# HIVE_BOARD_ETHERNET.net
KiCad netlist of a schematic drawn in Altium Designer
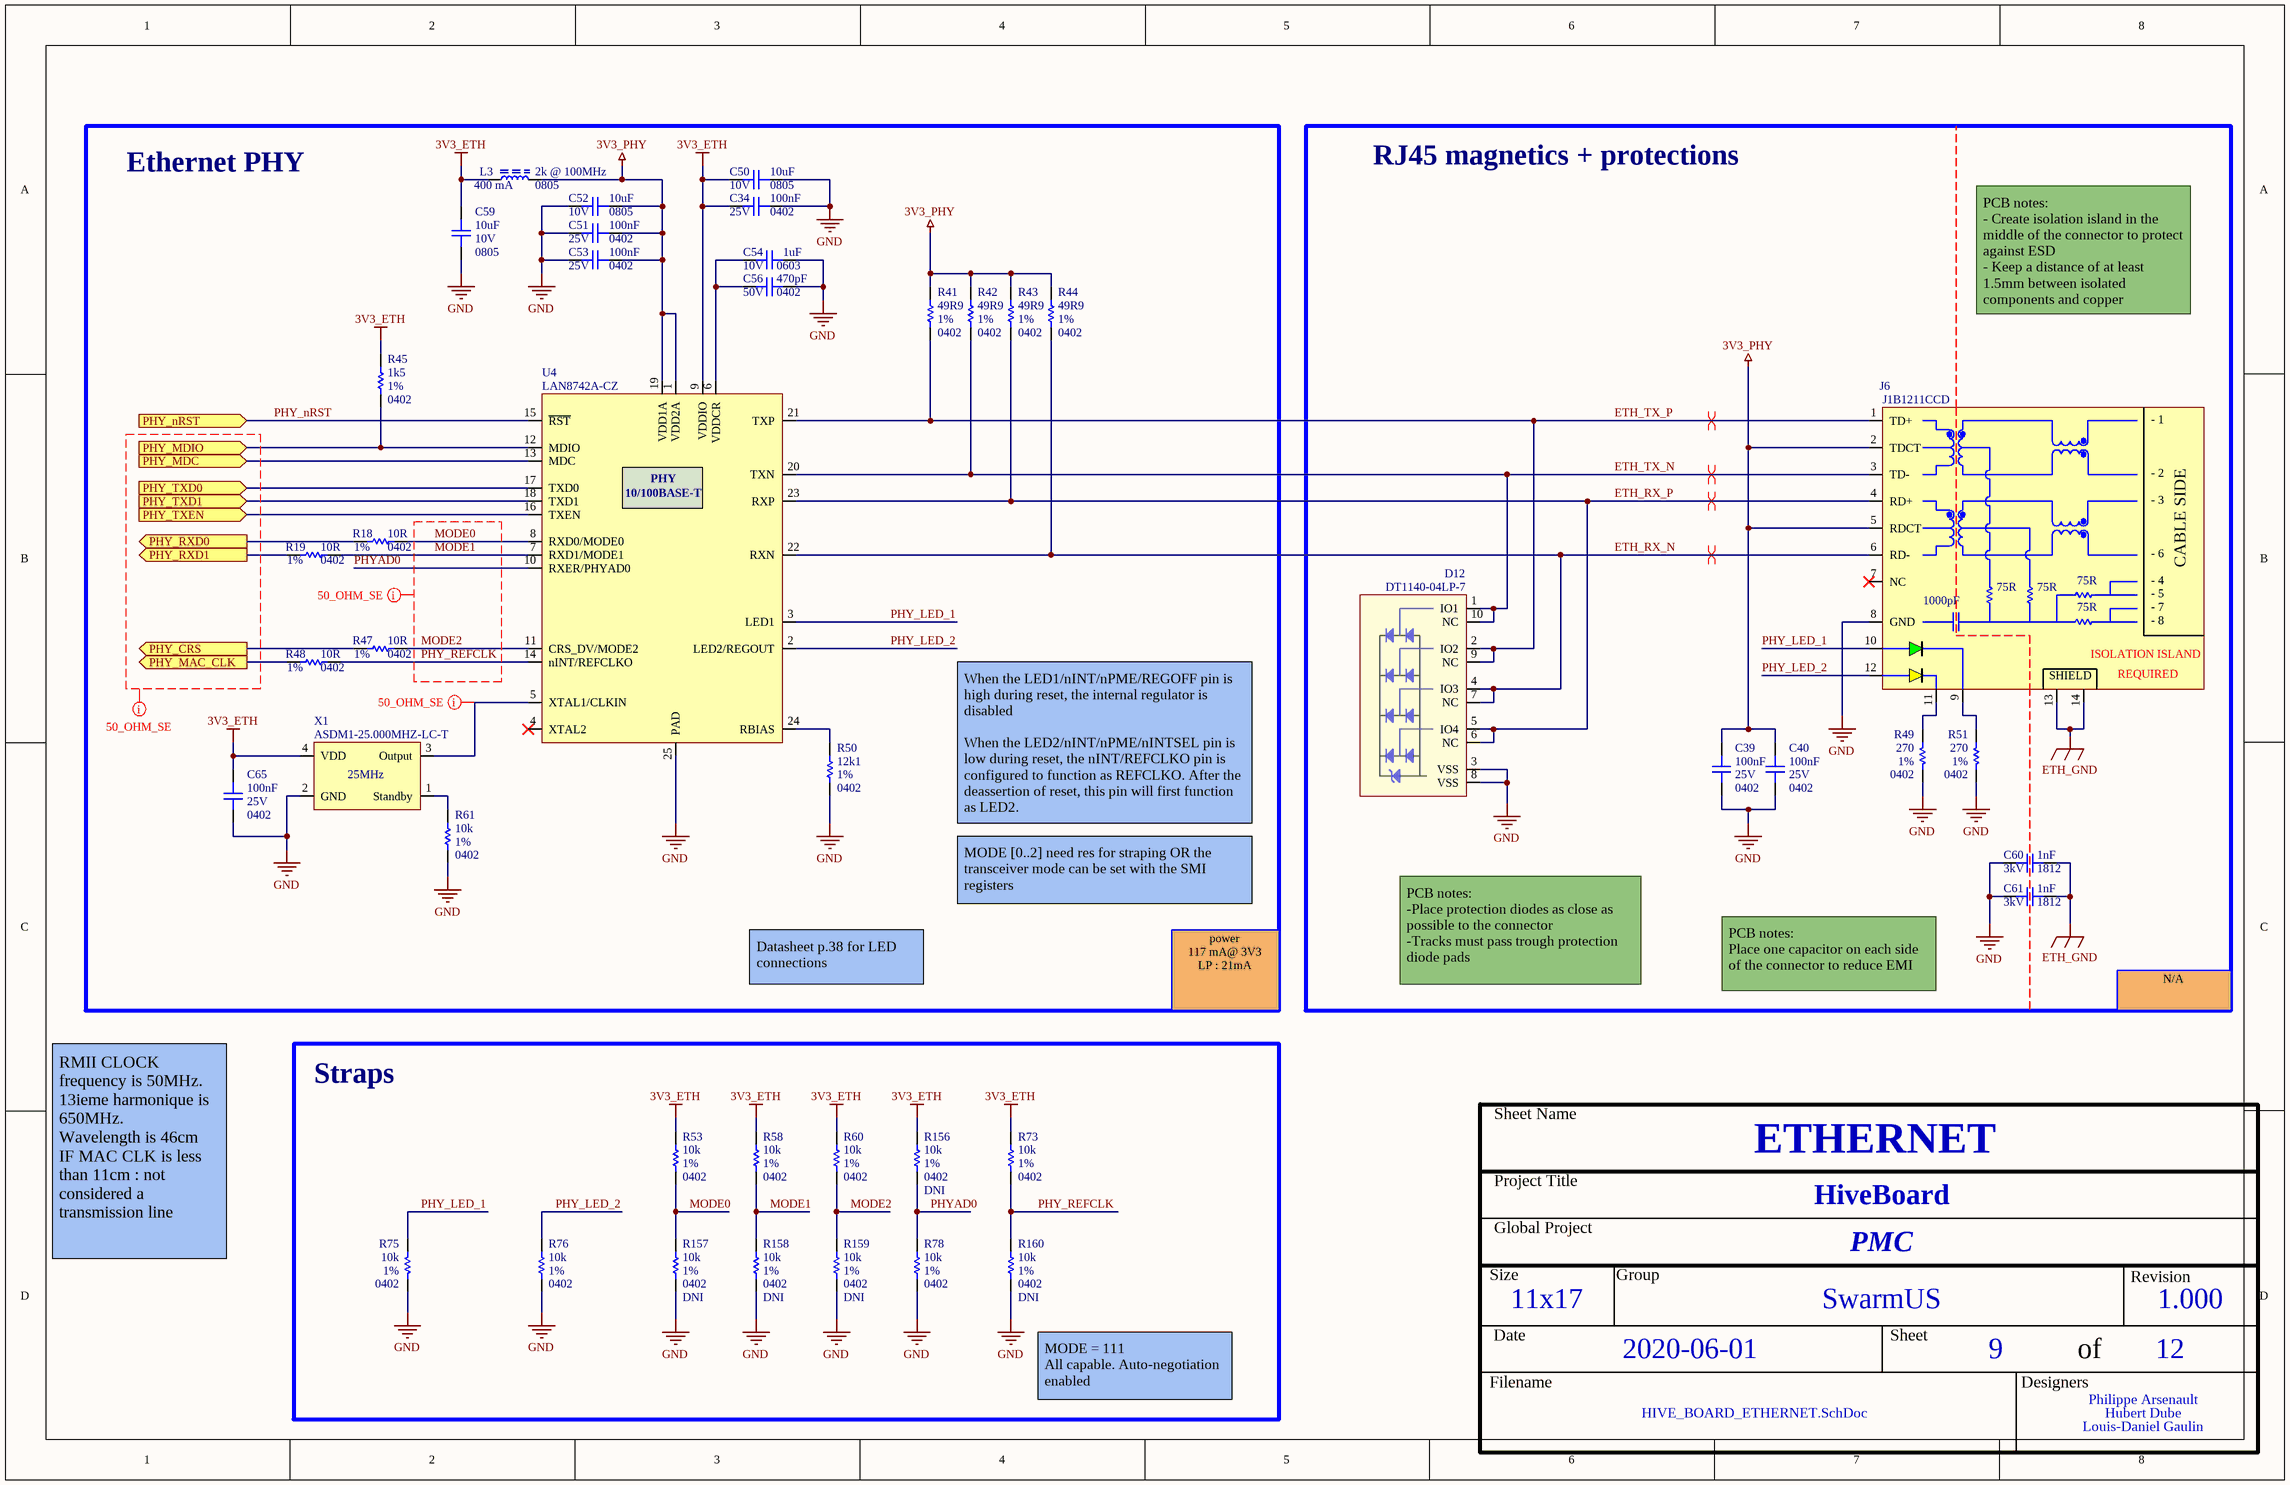
[diagram p0: HIVE_BOARD_ETHERNET.SchDoc]

(export (version "E")
  (design (tool "Eeschema 10.0.6"))
  (components
    (comp (ref "C34")
      (value "100nF")
      (footprint "CAP_CER_0402")
      (description "CAP - CER 0.1µF 10% 25V X7R - 0402")
      (fields
        (field (name "TOLERANCE") "10%")
        (field (name "PACKAGE") "0402")
        (field (name "VOLTAGE RATING") "25V")
        (field (name "Comment") "CGA2B3X7R1E104K050BB")
        (field (name "CREATEDBY/DATE") "Nicolas Roy 2018-11-07")
        (field (name "VERIFIEDBY") "Nicolas V. (2019-01-22)")
      )
      (libsource (lib "GRAMS_MASTER_LIB") (part "CAP_CER_CGA2B3X7R1E104K050BB"))
    )
    (comp (ref "C39")
      (value "100nF")
      (footprint "CAP_CER_0402")
      (description "CAP - CER 0.1µF 10% 25V X7R - 0402")
      (fields
        (field (name "TOLERANCE") "10%")
        (field (name "PACKAGE") "0402")
        (field (name "VOLTAGE RATING") "25V")
        (field (name "Comment") "CGA2B3X7R1E104K050BB")
        (field (name "CREATEDBY/DATE") "Nicolas Roy 2018-11-07")
        (field (name "VERIFIEDBY") "Nicolas V. (2019-01-22)")
      )
      (libsource (lib "GRAMS_MASTER_LIB") (part "CAP_CER_CGA2B3X7R1E104K050BB"))
    )
    (comp (ref "C40")
      (value "100nF")
      (footprint "CAP_CER_0402")
      (description "CAP - CER 0.1µF 10% 25V X7R - 0402")
      (fields
        (field (name "TOLERANCE") "10%")
        (field (name "PACKAGE") "0402")
        (field (name "VOLTAGE RATING") "25V")
        (field (name "Comment") "CGA2B3X7R1E104K050BB")
        (field (name "CREATEDBY/DATE") "Nicolas Roy 2018-11-07")
        (field (name "VERIFIEDBY") "Nicolas V. (2019-01-22)")
      )
      (libsource (lib "GRAMS_MASTER_LIB") (part "CAP_CER_CGA2B3X7R1E104K050BB"))
    )
    (comp (ref "C50")
      (value "10uF")
      (footprint "CAP_CER_0805")
      (description "CAP - CER 10UF 10% 10V X5R - 0805")
      (fields
        (field (name "TOLERANCE") "10%")
        (field (name "PACKAGE") "0805")
        (field (name "VOLTAGE RATING") "10V")
        (field (name "Comment") "LMK212BJ106KG-T")
        (field (name "CREATEDBY/DATE") "Caroline Paulin / 25 juillet 2018")
        (field (name "VERIFIEDBY") "Nicolas V. (2019-01-22)")
      )
      (libsource (lib "GRAMS_MASTER_LIB") (part "CAP_CER_LMK212BJ106KG-T"))
    )
    (comp (ref "C51")
      (value "100nF")
      (footprint "CAP_CER_0402")
      (description "CAP - CER 0.1µF 10% 25V X7R - 0402")
      (fields
        (field (name "TOLERANCE") "10%")
        (field (name "PACKAGE") "0402")
        (field (name "VOLTAGE RATING") "25V")
        (field (name "Comment") "CGA2B3X7R1E104K050BB")
        (field (name "CREATEDBY/DATE") "Nicolas Roy 2018-11-07")
        (field (name "VERIFIEDBY") "Nicolas V. (2019-01-22)")
      )
      (libsource (lib "GRAMS_MASTER_LIB") (part "CAP_CER_CGA2B3X7R1E104K050BB"))
    )
    (comp (ref "C52")
      (value "10uF")
      (footprint "CAP_CER_0805")
      (description "CAP - CER 10UF 10% 10V X5R - 0805")
      (fields
        (field (name "TOLERANCE") "10%")
        (field (name "PACKAGE") "0805")
        (field (name "VOLTAGE RATING") "10V")
        (field (name "Comment") "LMK212BJ106KG-T")
        (field (name "CREATEDBY/DATE") "Caroline Paulin / 25 juillet 2018")
        (field (name "VERIFIEDBY") "Nicolas V. (2019-01-22)")
      )
      (libsource (lib "GRAMS_MASTER_LIB") (part "CAP_CER_LMK212BJ106KG-T"))
    )
    (comp (ref "C53")
      (value "100nF")
      (footprint "CAP_CER_0402")
      (description "CAP - CER 0.1µF 10% 25V X7R - 0402")
      (fields
        (field (name "TOLERANCE") "10%")
        (field (name "PACKAGE") "0402")
        (field (name "VOLTAGE RATING") "25V")
        (field (name "Comment") "CGA2B3X7R1E104K050BB")
        (field (name "CREATEDBY/DATE") "Nicolas Roy 2018-11-07")
        (field (name "VERIFIEDBY") "Nicolas V. (2019-01-22)")
      )
      (libsource (lib "GRAMS_MASTER_LIB") (part "CAP_CER_CGA2B3X7R1E104K050BB"))
    )
    (comp (ref "C54")
      (value "1uF")
      (footprint "CAP_CER_0603")
      (description "CAP - CER 1uF 10V 10% X5R - 0603")
      (fields
        (field (name "TOLERANCE") "10%")
        (field (name "PACKAGE") "0603")
        (field (name "VOLTAGE RATING") "10V")
        (field (name "Comment") "C0603C105K8PACTU")
        (field (name "CREATEDBY/DATE") "Hubert Dube - 21/07/20")
        (field (name "VERIFIEDBY") "Louis-Daniel Gaulin - 21/07/20")
      )
      (libsource (lib "SWARMUS_LIB") (part "CAP_CER_C0603C105K8PACTU"))
    )
    (comp (ref "C56")
      (value "470pF")
      (footprint "CAP_CER_0402")
      (description "CAP - CER 470pF 10% 50V X7R - 0402")
      (fields
        (field (name "TOLERANCE") "10%")
        (field (name "PACKAGE") "0402")
        (field (name "VOLTAGE RATING") "50V")
        (field (name "Comment") "CC0402KRX7R9BB471")
        (field (name "CREATEDBY/DATE") "Nicolas Roy 2018-10-17")
        (field (name "VERIFIEDBY") "Caroline Paulin - 18 janv 2019")
      )
      (libsource (lib "GRAMS_MASTER_LIB") (part "CAP_CER_CC0402KRX7R9BB471"))
    )
    (comp (ref "C59")
      (value "10uF")
      (footprint "CAP_CER_0805")
      (description "CAP - CER 10UF 10% 10V X5R - 0805")
      (fields
        (field (name "TOLERANCE") "10%")
        (field (name "PACKAGE") "0805")
        (field (name "VOLTAGE RATING") "10V")
        (field (name "Comment") "LMK212BJ106KG-T")
        (field (name "CREATEDBY/DATE") "Caroline Paulin / 25 juillet 2018")
        (field (name "VERIFIEDBY") "Nicolas V. (2019-01-22)")
      )
      (libsource (lib "GRAMS_MASTER_LIB") (part "CAP_CER_LMK212BJ106KG-T"))
    )
    (comp (ref "C60")
      (value "1nF")
      (footprint "CAP_CER_1812")
      (description "CAP - CER 1000pF ±10% 3000V X7R")
      (fields
        (field (name "TOLERANCE") "10%")
        (field (name "PACKAGE") "1812")
        (field (name "VOLTAGE RATING") "3kV")
        (field (name "Comment") "885342211009")
        (field (name "CREATEDBY/DATE") "Hubert Dube - 03/02/2021")
        (field (name "VERIFIEDBY") "Philippe Asenault - 08-02-2021")
      )
      (libsource (lib "SWARMUS_LIB") (part "CAP_CER_885342211009"))
    )
    (comp (ref "C61")
      (value "1nF")
      (footprint "CAP_CER_1812")
      (description "CAP - CER 1000pF ±10% 3000V X7R")
      (fields
        (field (name "TOLERANCE") "10%")
        (field (name "PACKAGE") "1812")
        (field (name "VOLTAGE RATING") "3kV")
        (field (name "Comment") "885342211009")
        (field (name "CREATEDBY/DATE") "Hubert Dube - 03/02/2021")
        (field (name "VERIFIEDBY") "Philippe Asenault - 08-02-2021")
      )
      (libsource (lib "SWARMUS_LIB") (part "CAP_CER_885342211009"))
    )
    (comp (ref "C65")
      (value "100nF")
      (footprint "CAP_CER_0402")
      (description "CAP - CER 0.1µF 10% 25V X7R - 0402")
      (fields
        (field (name "TOLERANCE") "10%")
        (field (name "PACKAGE") "0402")
        (field (name "VOLTAGE RATING") "25V")
        (field (name "Comment") "CGA2B3X7R1E104K050BB")
        (field (name "CREATEDBY/DATE") "Nicolas Roy 2018-11-07")
        (field (name "VERIFIEDBY") "Nicolas V. (2019-01-22)")
      )
      (libsource (lib "GRAMS_MASTER_LIB") (part "CAP_CER_CGA2B3X7R1E104K050BB"))
    )
    (comp (ref "D12")
      (value "DT1140-04LP-7")
      (footprint "TVS_DATA_DT1140-04LP-7")
      (description "TVS - DIODE 5.5V 10V - 10-UFDFN")
      (fields
        (field (name "CREATEDBY/DATE") "Joël Lemay 2019-11-20")
        (field (name "VERIFIEDBY") "C.Paulin - 21/11/2019")
      )
      (libsource (lib "GRAMS_MASTER_LIB") (part "TVS_DATA_DT1140-04LP-7"))
    )
    (comp (ref "J6")
      (value "J1B1211CCD")
      (footprint "CON_ETH_J1B1211CCD_WIZ")
      (fields
        (field (name "CREATEDBY/DATE") "Hubert Dube - 12/02/2021")
        (field (name "VERIFIEDBY") "Philippe Arsenault - 2021-03-10")
      )
      (libsource (lib "SWARMUS_LIB") (part "CON_ETH_J1B1211CCD"))
    )
    (comp (ref "L3")
      (value "2k @ 100MHz")
      (footprint "FER_0805")
      (description "FER - FERRITE BEAD 2 KOHM @ 100 MHz 400 mA - 0805")
      (fields
        (field (name "CURRENT RATING") "400 mA")
        (field (name "PACKAGE") "0805")
        (field (name "Comment") "MMZ2012Y202BT000")
        (field (name "CREATEDBY/DATE") "Hubert Dube - 7/02/2021")
        (field (name "VERIFIEDBY") "Philippe Arsenault/ 2021-03-13")
      )
      (libsource (lib "SWARMUS_LIB") (part "FER_MMZ2012Y202BT000"))
    )
    (comp (ref "R18")
      (value "10R")
      (footprint "RES_0402")
      (description "RES - 10R 1% 1/16W - 0402")
      (fields
        (field (name "TOLERANCE") "1%")
        (field (name "PACKAGE") "0402")
        (field (name "Comment") "RMCF0402FT10R0")
        (field (name "CREATEDBY/DATE") "Joel Lemay 2018-07-04")
        (field (name "VERIFIEDBY") "Caroline Paulin - 6 sept 2018")
      )
      (libsource (lib "GRAMS_MASTER_LIB") (part "RES_RMCF0402FT10R0"))
    )
    (comp (ref "R19")
      (value "10R")
      (footprint "RES_0402")
      (description "RES - 10R 1% 1/16W - 0402")
      (fields
        (field (name "TOLERANCE") "1%")
        (field (name "PACKAGE") "0402")
        (field (name "Comment") "RMCF0402FT10R0")
        (field (name "CREATEDBY/DATE") "Joel Lemay 2018-07-04")
        (field (name "VERIFIEDBY") "Caroline Paulin - 6 sept 2018")
      )
      (libsource (lib "GRAMS_MASTER_LIB") (part "RES_RMCF0402FT10R0"))
    )
    (comp (ref "R41")
      (value "49R9")
      (footprint "RES_0402")
      (description "RES - 49.9 R ±1% 1/16W -  0402")
      (fields
        (field (name "TOLERANCE") "1%")
        (field (name "PACKAGE") "0402")
        (field (name "Comment") "RC0402FR-0749R9L")
        (field (name "CREATEDBY/DATE") "Hubert Dubé - 3/02/2020")
        (field (name "VERIFIEDBY") "Philippe Arsenault/2021-02-08")
      )
      (libsource (lib "SWARMUS_LIB") (part "RES_RC0402FR-0749R9L"))
    )
    (comp (ref "R42")
      (value "49R9")
      (footprint "RES_0402")
      (description "RES - 49.9 R ±1% 1/16W -  0402")
      (fields
        (field (name "TOLERANCE") "1%")
        (field (name "PACKAGE") "0402")
        (field (name "Comment") "RC0402FR-0749R9L")
        (field (name "CREATEDBY/DATE") "Hubert Dubé - 3/02/2020")
        (field (name "VERIFIEDBY") "Philippe Arsenault/2021-02-08")
      )
      (libsource (lib "SWARMUS_LIB") (part "RES_RC0402FR-0749R9L"))
    )
    (comp (ref "R43")
      (value "49R9")
      (footprint "RES_0402")
      (description "RES - 49.9 R ±1% 1/16W -  0402")
      (fields
        (field (name "TOLERANCE") "1%")
        (field (name "PACKAGE") "0402")
        (field (name "Comment") "RC0402FR-0749R9L")
        (field (name "CREATEDBY/DATE") "Hubert Dubé - 3/02/2020")
        (field (name "VERIFIEDBY") "Philippe Arsenault/2021-02-08")
      )
      (libsource (lib "SWARMUS_LIB") (part "RES_RC0402FR-0749R9L"))
    )
    (comp (ref "R44")
      (value "49R9")
      (footprint "RES_0402")
      (description "RES - 49.9 R ±1% 1/16W -  0402")
      (fields
        (field (name "TOLERANCE") "1%")
        (field (name "PACKAGE") "0402")
        (field (name "Comment") "RC0402FR-0749R9L")
        (field (name "CREATEDBY/DATE") "Hubert Dubé - 3/02/2020")
        (field (name "VERIFIEDBY") "Philippe Arsenault/2021-02-08")
      )
      (libsource (lib "SWARMUS_LIB") (part "RES_RC0402FR-0749R9L"))
    )
    (comp (ref "R45")
      (value "1k5")
      (footprint "RES_0402")
      (description "RES - 1.5K 1% 1/16W - 0402")
      (fields
        (field (name "TOLERANCE") "1%")
        (field (name "PACKAGE") "0402")
        (field (name "Comment") "RC0402FR-071K5L")
        (field (name "CREATEDBY/DATE") "Philippe Arsenault/21 Janvier 2020")
        (field (name "VERIFIEDBY") "C.Paulin - 28/01/2020")
      )
      (libsource (lib "GRAMS_MASTER_LIB") (part "RES_RC0402FR-071K5L"))
    )
    (comp (ref "R47")
      (value "10R")
      (footprint "RES_0402")
      (description "RES - 10R 1% 1/16W - 0402")
      (fields
        (field (name "TOLERANCE") "1%")
        (field (name "PACKAGE") "0402")
        (field (name "Comment") "RMCF0402FT10R0")
        (field (name "CREATEDBY/DATE") "Joel Lemay 2018-07-04")
        (field (name "VERIFIEDBY") "Caroline Paulin - 6 sept 2018")
      )
      (libsource (lib "GRAMS_MASTER_LIB") (part "RES_RMCF0402FT10R0"))
    )
    (comp (ref "R48")
      (value "10R")
      (footprint "RES_0402")
      (description "RES - 10R 1% 1/16W - 0402")
      (fields
        (field (name "TOLERANCE") "1%")
        (field (name "PACKAGE") "0402")
        (field (name "Comment") "RMCF0402FT10R0")
        (field (name "CREATEDBY/DATE") "Joel Lemay 2018-07-04")
        (field (name "VERIFIEDBY") "Caroline Paulin - 6 sept 2018")
      )
      (libsource (lib "GRAMS_MASTER_LIB") (part "RES_RMCF0402FT10R0"))
    )
    (comp (ref "R49")
      (value "270")
      (footprint "FER_0402")
      (description "RES - 270R 1% 1/16W - 0402")
      (fields
        (field (name "TOLERANCE") "1%")
        (field (name "PACKAGE") "0402")
        (field (name "Comment") "RC0402FR-07270RL")
        (field (name "CREATEDBY/DATE") "Philippe Arsenault 2020-07-24")
        (field (name "VERIFIEDBY") "Louis-Daniel Gaulin / 03-10-2020")
      )
      (libsource (lib "SWARMUS_LIB") (part "RES_RC0402FR-07270RL"))
    )
    (comp (ref "R50")
      (value "12k1")
      (footprint "RES_0402")
      (description "RES - 12K1 ±1% 1/16W - 0402")
      (fields
        (field (name "TOLERANCE") "1%")
        (field (name "PACKAGE") "0402")
        (field (name "Comment") "RC0402FR-0712K1L")
        (field (name "CREATEDBY/DATE") "Hubert Dubé - 7/02/2020")
        (field (name "VERIFIEDBY") "Philippe Arsenault/2021-02-08")
      )
      (libsource (lib "SWARMUS_LIB") (part "RES_RC0402FR-0712K1L"))
    )
    (comp (ref "R51")
      (value "270")
      (footprint "FER_0402")
      (description "RES - 270R 1% 1/16W - 0402")
      (fields
        (field (name "TOLERANCE") "1%")
        (field (name "PACKAGE") "0402")
        (field (name "Comment") "RC0402FR-07270RL")
        (field (name "CREATEDBY/DATE") "Philippe Arsenault 2020-07-24")
        (field (name "VERIFIEDBY") "Louis-Daniel Gaulin / 03-10-2020")
      )
      (libsource (lib "SWARMUS_LIB") (part "RES_RC0402FR-07270RL"))
    )
    (comp (ref "R53")
      (value "10k")
      (footprint "RES_0402")
      (description "RES - 10K OHMS 1% 1/16W - 0402")
      (fields
        (field (name "TOLERANCE") "1%")
        (field (name "PACKAGE") "0402")
        (field (name "Comment") "RC0402FR-0710KL")
        (field (name "CREATEDBY/DATE") "Nicolas V. (2018-11-20)")
        (field (name "VERIFIEDBY") "Nicolas V. (2018-11-20)")
      )
      (libsource (lib "GRAMS_MASTER_LIB") (part "RES_RC0402FR-0710KL"))
    )
    (comp (ref "R58")
      (value "10k")
      (footprint "RES_0402")
      (description "RES - 10K OHMS 1% 1/16W - 0402")
      (fields
        (field (name "TOLERANCE") "1%")
        (field (name "PACKAGE") "0402")
        (field (name "Comment") "RC0402FR-0710KL")
        (field (name "CREATEDBY/DATE") "Nicolas V. (2018-11-20)")
        (field (name "VERIFIEDBY") "Nicolas V. (2018-11-20)")
      )
      (libsource (lib "GRAMS_MASTER_LIB") (part "RES_RC0402FR-0710KL"))
    )
    (comp (ref "R60")
      (value "10k")
      (footprint "RES_0402")
      (description "RES - 10K OHMS 1% 1/16W - 0402")
      (fields
        (field (name "TOLERANCE") "1%")
        (field (name "PACKAGE") "0402")
        (field (name "Comment") "RC0402FR-0710KL")
        (field (name "CREATEDBY/DATE") "Nicolas V. (2018-11-20)")
        (field (name "VERIFIEDBY") "Nicolas V. (2018-11-20)")
      )
      (libsource (lib "GRAMS_MASTER_LIB") (part "RES_RC0402FR-0710KL"))
    )
    (comp (ref "R61")
      (value "10k")
      (footprint "RES_0402")
      (description "RES - 10K OHMS 1% 1/16W - 0402")
      (fields
        (field (name "TOLERANCE") "1%")
        (field (name "PACKAGE") "0402")
        (field (name "Comment") "RC0402FR-0710KL")
        (field (name "CREATEDBY/DATE") "Nicolas V. (2018-11-20)")
        (field (name "VERIFIEDBY") "Nicolas V. (2018-11-20)")
      )
      (libsource (lib "GRAMS_MASTER_LIB") (part "RES_RC0402FR-0710KL"))
    )
    (comp (ref "R73")
      (value "10k")
      (footprint "RES_0402")
      (description "RES - 10K OHMS 1% 1/16W - 0402")
      (fields
        (field (name "TOLERANCE") "1%")
        (field (name "PACKAGE") "0402")
        (field (name "Comment") "RC0402FR-0710KL")
        (field (name "CREATEDBY/DATE") "Nicolas V. (2018-11-20)")
        (field (name "VERIFIEDBY") "Nicolas V. (2018-11-20)")
      )
      (libsource (lib "GRAMS_MASTER_LIB") (part "RES_RC0402FR-0710KL"))
    )
    (comp (ref "R75")
      (value "10k")
      (footprint "RES_0402")
      (description "RES - 10K OHMS 1% 1/16W - 0402")
      (fields
        (field (name "TOLERANCE") "1%")
        (field (name "PACKAGE") "0402")
        (field (name "Comment") "RC0402FR-0710KL")
        (field (name "CREATEDBY/DATE") "Nicolas V. (2018-11-20)")
        (field (name "VERIFIEDBY") "Nicolas V. (2018-11-20)")
      )
      (libsource (lib "GRAMS_MASTER_LIB") (part "RES_RC0402FR-0710KL"))
    )
    (comp (ref "R76")
      (value "10k")
      (footprint "RES_0402")
      (description "RES - 10K OHMS 1% 1/16W - 0402")
      (fields
        (field (name "TOLERANCE") "1%")
        (field (name "PACKAGE") "0402")
        (field (name "Comment") "RC0402FR-0710KL")
        (field (name "CREATEDBY/DATE") "Nicolas V. (2018-11-20)")
        (field (name "VERIFIEDBY") "Nicolas V. (2018-11-20)")
      )
      (libsource (lib "GRAMS_MASTER_LIB") (part "RES_RC0402FR-0710KL"))
    )
    (comp (ref "R78")
      (value "10k")
      (footprint "RES_0402")
      (description "RES - 10K OHMS 1% 1/16W - 0402")
      (fields
        (field (name "TOLERANCE") "1%")
        (field (name "PACKAGE") "0402")
        (field (name "Comment") "RC0402FR-0710KL")
        (field (name "CREATEDBY/DATE") "Nicolas V. (2018-11-20)")
        (field (name "VERIFIEDBY") "Nicolas V. (2018-11-20)")
      )
      (libsource (lib "GRAMS_MASTER_LIB") (part "RES_RC0402FR-0710KL"))
    )
    (comp (ref "R156")
      (value "10k")
      (footprint "RES_0402")
      (description "RES - 10K OHMS 1% 1/16W - 0402")
      (fields
        (field (name "TOLERANCE") "1%")
        (field (name "ASSEMBLY NOTE") "DNI")
        (field (name "PACKAGE") "0402")
        (field (name "Comment") "RC0402FR-0710KL")
        (field (name "CREATEDBY/DATE") "Nicolas V. (2018-11-20)")
        (field (name "VERIFIEDBY") "Nicolas V. (2018-11-20)")
      )
      (libsource (lib "GRAMS_MASTER_LIB") (part "RES_RC0402FR-0710KL"))
    )
    (comp (ref "R157")
      (value "10k")
      (footprint "RES_0402")
      (description "RES - 10K OHMS 1% 1/16W - 0402")
      (fields
        (field (name "TOLERANCE") "1%")
        (field (name "ASSEMBLY NOTE") "DNI")
        (field (name "PACKAGE") "0402")
        (field (name "Comment") "RC0402FR-0710KL")
        (field (name "CREATEDBY/DATE") "Nicolas V. (2018-11-20)")
        (field (name "VERIFIEDBY") "Nicolas V. (2018-11-20)")
      )
      (libsource (lib "GRAMS_MASTER_LIB") (part "RES_RC0402FR-0710KL"))
    )
    (comp (ref "R158")
      (value "10k")
      (footprint "RES_0402")
      (description "RES - 10K OHMS 1% 1/16W - 0402")
      (fields
        (field (name "TOLERANCE") "1%")
        (field (name "ASSEMBLY NOTE") "DNI")
        (field (name "PACKAGE") "0402")
        (field (name "Comment") "RC0402FR-0710KL")
        (field (name "CREATEDBY/DATE") "Nicolas V. (2018-11-20)")
        (field (name "VERIFIEDBY") "Nicolas V. (2018-11-20)")
      )
      (libsource (lib "GRAMS_MASTER_LIB") (part "RES_RC0402FR-0710KL"))
    )
    (comp (ref "R159")
      (value "10k")
      (footprint "RES_0402")
      (description "RES - 10K OHMS 1% 1/16W - 0402")
      (fields
        (field (name "TOLERANCE") "1%")
        (field (name "ASSEMBLY NOTE") "DNI")
        (field (name "PACKAGE") "0402")
        (field (name "Comment") "RC0402FR-0710KL")
        (field (name "CREATEDBY/DATE") "Nicolas V. (2018-11-20)")
        (field (name "VERIFIEDBY") "Nicolas V. (2018-11-20)")
      )
      (libsource (lib "GRAMS_MASTER_LIB") (part "RES_RC0402FR-0710KL"))
    )
    (comp (ref "R160")
      (value "10k")
      (footprint "RES_0402")
      (description "RES - 10K OHMS 1% 1/16W - 0402")
      (fields
        (field (name "TOLERANCE") "1%")
        (field (name "ASSEMBLY NOTE") "DNI")
        (field (name "PACKAGE") "0402")
        (field (name "Comment") "RC0402FR-0710KL")
        (field (name "CREATEDBY/DATE") "Nicolas V. (2018-11-20)")
        (field (name "VERIFIEDBY") "Nicolas V. (2018-11-20)")
      )
      (libsource (lib "GRAMS_MASTER_LIB") (part "RES_RC0402FR-0710KL"))
    )
    (comp (ref "U4")
      (value "LAN8742A-CZ")
      (footprint "COM_ETH_LAN8742A-CZ-TR")
      (description "COM_ETH_ Ethernet PHY 1/1 Transceiver  Ethernet 24-SQFN (4x4) 10/100 BASE-T")
      (fields
        (field (name "VERIFIEDBY") "Philippe Arsenault 2021-03-10")
        (field (name "CREATEDBY/DATE") "Hubert Dube -  28/01/2021")
      )
      (libsource (lib "SWARMUS_LIB") (part "COM_ETH_LAN8742A-CZ"))
    )
    (comp (ref "X1")
      (value "ASDM1-25.000MHZ-LC-T")
      (footprint "OSC_CRY_ASDM1-25.000MHZ-LC-T")
      (description "OSC_CRY - 25MHz +-50ppm LVCMOS Crystal")
      (fields
        (field (name "CREATEDBY/DATE") "Philippe Arsenault/2021-04-07")
        (field (name "VERIFIEDBY") "Louis-Daniel Gaulin / 08-04-2021")
      )
      (libsource (lib "SWARMUS_LIB") (part "OSC_CRY_ASDM1-25.000MHZ-LC-T"))
    )
  )
  (nets
    (net (code "1") (name "/ETH_RX_N") (class "Default")
      (node (ref "D12") (pin "4") (pinfunction "IO3_4") (pintype "passive"))
      (node (ref "D12") (pin "7") (pinfunction "NC_7") (pintype "passive"))
      (node (ref "J6") (pin "6") (pinfunction "RD-_6") (pintype "passive"))
      (node (ref "R44") (pin "1") (pinfunction "1_1") (pintype "passive"))
      (node (ref "U4") (pin "22") (pinfunction "RXN_22") (pintype "passive"))
    )
    (net (code "2") (name "/ETH_RX_P") (class "Default")
      (node (ref "D12") (pin "5") (pinfunction "IO4_5") (pintype "passive"))
      (node (ref "D12") (pin "6") (pinfunction "NC_6") (pintype "passive"))
      (node (ref "J6") (pin "4") (pinfunction "RD+_4") (pintype "passive"))
      (node (ref "R43") (pin "1") (pinfunction "1_1") (pintype "passive"))
      (node (ref "U4") (pin "23") (pinfunction "RXP_23") (pintype "passive"))
    )
    (net (code "3") (name "/ETH_TX_N") (class "Default")
      (node (ref "D12") (pin "1") (pinfunction "IO1_1") (pintype "passive"))
      (node (ref "D12") (pin "10") (pinfunction "NC_10") (pintype "passive"))
      (node (ref "J6") (pin "3") (pinfunction "TD-_3") (pintype "passive"))
      (node (ref "R42") (pin "1") (pinfunction "1_1") (pintype "passive"))
      (node (ref "U4") (pin "20") (pinfunction "TXN_20") (pintype "passive"))
    )
    (net (code "4") (name "/ETH_TX_P") (class "Default")
      (node (ref "D12") (pin "2") (pinfunction "IO2_2") (pintype "passive"))
      (node (ref "D12") (pin "9") (pinfunction "NC_9") (pintype "passive"))
      (node (ref "J6") (pin "1") (pinfunction "TD+_1") (pintype "passive"))
      (node (ref "R41") (pin "1") (pinfunction "1_1") (pintype "passive"))
      (node (ref "U4") (pin "21") (pinfunction "TXP_21") (pintype "passive"))
    )
    (net (code "5") (name "/MODE0") (class "Default")
      (node (ref "R157") (pin "2") (pinfunction "2_2") (pintype "passive"))
      (node (ref "R18") (pin "1") (pinfunction "1_1") (pintype "passive"))
      (node (ref "R53") (pin "1") (pinfunction "1_1") (pintype "passive"))
      (node (ref "U4") (pin "8") (pinfunction "RXD0/MODE0_8") (pintype "passive"))
    )
    (net (code "6") (name "/MODE1") (class "Default")
      (node (ref "R158") (pin "2") (pinfunction "2_2") (pintype "passive"))
      (node (ref "R19") (pin "1") (pinfunction "1_1") (pintype "passive"))
      (node (ref "R58") (pin "1") (pinfunction "1_1") (pintype "passive"))
      (node (ref "U4") (pin "7") (pinfunction "RXD1/MODE1_7") (pintype "passive"))
    )
    (net (code "7") (name "/MODE2") (class "Default")
      (node (ref "R159") (pin "2") (pinfunction "2_2") (pintype "passive"))
      (node (ref "R47") (pin "1") (pinfunction "1_1") (pintype "passive"))
      (node (ref "R60") (pin "1") (pinfunction "1_1") (pintype "passive"))
      (node (ref "U4") (pin "11") (pinfunction "CRS_DV/MODE2_11") (pintype "passive"))
    )
    (net (code "8") (name "/PHYAD0") (class "Default")
      (node (ref "R156") (pin "1") (pinfunction "1_1") (pintype "passive"))
      (node (ref "R78") (pin "2") (pinfunction "2_2") (pintype "passive"))
      (node (ref "U4") (pin "10") (pinfunction "RXER/PHYAD0_10") (pintype "passive"))
    )
    (net (code "9") (name "/PHY_CRS") (class "Default")
      (node (ref "R47") (pin "2") (pinfunction "2_2") (pintype "passive"))
    )
    (net (code "10") (name "/PHY_LED_1") (class "Default")
      (node (ref "J6") (pin "10") (pinfunction "LED1_A_10") (pintype "passive"))
      (node (ref "R75") (pin "2") (pinfunction "2_2") (pintype "passive"))
      (node (ref "U4") (pin "3") (pinfunction "LED1_3") (pintype "passive"))
    )
    (net (code "11") (name "/PHY_LED_2") (class "Default")
      (node (ref "J6") (pin "12") (pintype "passive"))
      (node (ref "R76") (pin "2") (pinfunction "2_2") (pintype "passive"))
      (node (ref "U4") (pin "2") (pinfunction "LED2/REGOUT_2") (pintype "passive"))
    )
    (net (code "12") (name "/PHY_MAC_CLK") (class "Default")
      (node (ref "R48") (pin "2") (pinfunction "2_2") (pintype "passive"))
    )
    (net (code "13") (name "/PHY_MDC") (class "Default")
      (node (ref "U4") (pin "13") (pinfunction "MDC_13") (pintype "passive"))
    )
    (net (code "14") (name "/PHY_MDIO") (class "Default")
      (node (ref "R45") (pin "1") (pinfunction "1_1") (pintype "passive"))
      (node (ref "U4") (pin "12") (pinfunction "MDIO_12") (pintype "passive"))
    )
    (net (code "15") (name "/PHY_REFCLK") (class "Default")
      (node (ref "R160") (pin "2") (pinfunction "2_2") (pintype "passive"))
      (node (ref "R48") (pin "1") (pinfunction "1_1") (pintype "passive"))
      (node (ref "R73") (pin "1") (pinfunction "1_1") (pintype "passive"))
      (node (ref "U4") (pin "14") (pinfunction "nINT/REFCLKO_14") (pintype "passive"))
    )
    (net (code "16") (name "/PHY_RXD0") (class "Default")
      (node (ref "R18") (pin "2") (pinfunction "2_2") (pintype "passive"))
    )
    (net (code "17") (name "/PHY_RXD1") (class "Default")
      (node (ref "R19") (pin "2") (pinfunction "2_2") (pintype "passive"))
    )
    (net (code "18") (name "/PHY_TXD0") (class "Default")
      (node (ref "U4") (pin "17") (pinfunction "TXD0_17") (pintype "passive"))
    )
    (net (code "19") (name "/PHY_TXD1") (class "Default")
      (node (ref "U4") (pin "18") (pinfunction "TXD1_18") (pintype "passive"))
    )
    (net (code "20") (name "/PHY_TXEN") (class "Default")
      (node (ref "U4") (pin "16") (pinfunction "TXEN_16") (pintype "passive"))
    )
    (net (code "21") (name "/PHY_nRST") (class "Default")
      (node (ref "U4") (pin "15") (pinfunction "RST_15") (pintype "passive"))
    )
    (net (code "22") (name "3V3_ETH") (class "Default")
      (node (ref "C34") (pin "2") (pinfunction "2_2") (pintype "passive"))
      (node (ref "C50") (pin "2") (pinfunction "2_2") (pintype "passive"))
      (node (ref "C59") (pin "2") (pinfunction "2_2") (pintype "passive"))
      (node (ref "C65") (pin "1") (pinfunction "1_1") (pintype "passive"))
      (node (ref "L3") (pin "1") (pinfunction "1_1") (pintype "passive"))
      (node (ref "R156") (pin "2") (pinfunction "2_2") (pintype "passive"))
      (node (ref "R45") (pin "2") (pinfunction "2_2") (pintype "passive"))
      (node (ref "R53") (pin "2") (pinfunction "2_2") (pintype "passive"))
      (node (ref "R58") (pin "2") (pinfunction "2_2") (pintype "passive"))
      (node (ref "R60") (pin "2") (pinfunction "2_2") (pintype "passive"))
      (node (ref "R73") (pin "2") (pinfunction "2_2") (pintype "passive"))
      (node (ref "U4") (pin "9") (pinfunction "VDDIO_9") (pintype "passive"))
      (node (ref "X1") (pin "4") (pinfunction "VDD_4") (pintype "passive"))
    )
    (net (code "23") (name "3V3_PHY") (class "Default")
      (node (ref "C39") (pin "1") (pinfunction "1_1") (pintype "passive"))
      (node (ref "C40") (pin "1") (pinfunction "1_1") (pintype "passive"))
      (node (ref "C51") (pin "1") (pinfunction "1_1") (pintype "passive"))
      (node (ref "C52") (pin "1") (pinfunction "1_1") (pintype "passive"))
      (node (ref "C53") (pin "1") (pinfunction "1_1") (pintype "passive"))
      (node (ref "J6") (pin "2") (pinfunction "TDCT_2") (pintype "passive"))
      (node (ref "J6") (pin "5") (pinfunction "RDCT_5") (pintype "passive"))
      (node (ref "L3") (pin "2") (pinfunction "2_2") (pintype "passive"))
      (node (ref "R41") (pin "2") (pinfunction "2_2") (pintype "passive"))
      (node (ref "R42") (pin "2") (pinfunction "2_2") (pintype "passive"))
      (node (ref "R43") (pin "2") (pinfunction "2_2") (pintype "passive"))
      (node (ref "R44") (pin "2") (pinfunction "2_2") (pintype "passive"))
      (node (ref "U4") (pin "1") (pinfunction "VDD2A_1") (pintype "passive"))
      (node (ref "U4") (pin "19") (pinfunction "VDD1A_19") (pintype "passive"))
    )
    (net (code "24") (name "ETH_GND") (class "Default")
      (node (ref "C60") (pin "1") (pinfunction "1_1") (pintype "passive"))
      (node (ref "C61") (pin "1") (pinfunction "1_1") (pintype "passive"))
      (node (ref "J6") (pin "13") (pinfunction "SHIELD_13") (pintype "passive"))
      (node (ref "J6") (pin "14") (pintype "passive"))
    )
    (net (code "25") (name "GND") (class "Default")
      (node (ref "C34") (pin "1") (pinfunction "1_1") (pintype "passive"))
      (node (ref "C39") (pin "2") (pinfunction "2_2") (pintype "passive"))
      (node (ref "C40") (pin "2") (pinfunction "2_2") (pintype "passive"))
      (node (ref "C50") (pin "1") (pinfunction "1_1") (pintype "passive"))
      (node (ref "C51") (pin "2") (pinfunction "2_2") (pintype "passive"))
      (node (ref "C52") (pin "2") (pinfunction "2_2") (pintype "passive"))
      (node (ref "C53") (pin "2") (pinfunction "2_2") (pintype "passive"))
      (node (ref "C54") (pin "1") (pinfunction "1_1") (pintype "passive"))
      (node (ref "C56") (pin "1") (pinfunction "1_1") (pintype "passive"))
      (node (ref "C59") (pin "1") (pinfunction "1_1") (pintype "passive"))
      (node (ref "C60") (pin "2") (pinfunction "2_2") (pintype "passive"))
      (node (ref "C61") (pin "2") (pinfunction "2_2") (pintype "passive"))
      (node (ref "C65") (pin "2") (pinfunction "2_2") (pintype "passive"))
      (node (ref "D12") (pin "3") (pinfunction "VSS_3") (pintype "passive"))
      (node (ref "D12") (pin "8") (pinfunction "VSS_8") (pintype "passive"))
      (node (ref "J6") (pin "8") (pinfunction "GND_8") (pintype "passive"))
      (node (ref "R157") (pin "1") (pinfunction "1_1") (pintype "passive"))
      (node (ref "R158") (pin "1") (pinfunction "1_1") (pintype "passive"))
      (node (ref "R159") (pin "1") (pinfunction "1_1") (pintype "passive"))
      (node (ref "R160") (pin "1") (pinfunction "1_1") (pintype "passive"))
      (node (ref "R49") (pin "1") (pinfunction "1_1") (pintype "passive"))
      (node (ref "R50") (pin "1") (pinfunction "1_1") (pintype "passive"))
      (node (ref "R51") (pin "1") (pinfunction "1_1") (pintype "passive"))
      (node (ref "R61") (pin "1") (pinfunction "1_1") (pintype "passive"))
      (node (ref "R75") (pin "1") (pinfunction "1_1") (pintype "passive"))
      (node (ref "R76") (pin "1") (pinfunction "1_1") (pintype "passive"))
      (node (ref "R78") (pin "1") (pinfunction "1_1") (pintype "passive"))
      (node (ref "U4") (pin "25") (pinfunction "PAD_25") (pintype "passive"))
      (node (ref "X1") (pin "2") (pinfunction "GND_2") (pintype "passive"))
    )
    (net (code "26") (name "Net-(J6-LED1_K)") (class "Default")
      (node (ref "J6") (pin "9") (pinfunction "LED1_K_9") (pintype "passive"))
      (node (ref "R51") (pin "2") (pinfunction "2_2") (pintype "passive"))
    )
    (net (code "27") (name "Net-(J6-Pad11)") (class "Default")
      (node (ref "J6") (pin "11") (pintype "passive"))
      (node (ref "R49") (pin "2") (pinfunction "2_2") (pintype "passive"))
    )
    (net (code "28") (name "Net-(U4-RBIAS)") (class "Default")
      (node (ref "R50") (pin "2") (pinfunction "2_2") (pintype "passive"))
      (node (ref "U4") (pin "24") (pinfunction "RBIAS_24") (pintype "passive"))
    )
    (net (code "29") (name "Net-(U4-VDDCR)") (class "Default")
      (node (ref "C54") (pin "2") (pinfunction "2_2") (pintype "passive"))
      (node (ref "C56") (pin "2") (pinfunction "2_2") (pintype "passive"))
      (node (ref "U4") (pin "6") (pinfunction "VDDCR_6") (pintype "passive"))
    )
    (net (code "30") (name "Net-(U4-XTAL1{slash}CLKIN)") (class "Default")
      (node (ref "U4") (pin "5") (pinfunction "XTAL1/CLKIN_5") (pintype "passive"))
      (node (ref "X1") (pin "3") (pinfunction "Output_3") (pintype "passive"))
    )
    (net (code "31") (name "Net-(X1-Standby)") (class "Default")
      (node (ref "R61") (pin "2") (pinfunction "2_2") (pintype "passive"))
      (node (ref "X1") (pin "1") (pinfunction "Standby_1") (pintype "passive"))
    )
    (net (code "32") (name "unconnected-(J6-NC-Pad7)") (class "Default")
      (node (ref "J6") (pin "7") (pinfunction "NC_7") (pintype "passive+no_connect"))
    )
    (net (code "33") (name "unconnected-(U4-XTAL2-Pad4)") (class "Default")
      (node (ref "U4") (pin "4") (pinfunction "XTAL2_4") (pintype "passive+no_connect"))
    )
  )
)
